# DAQ_Board.net
KiCad netlist of a schematic drawn in Altium Designer
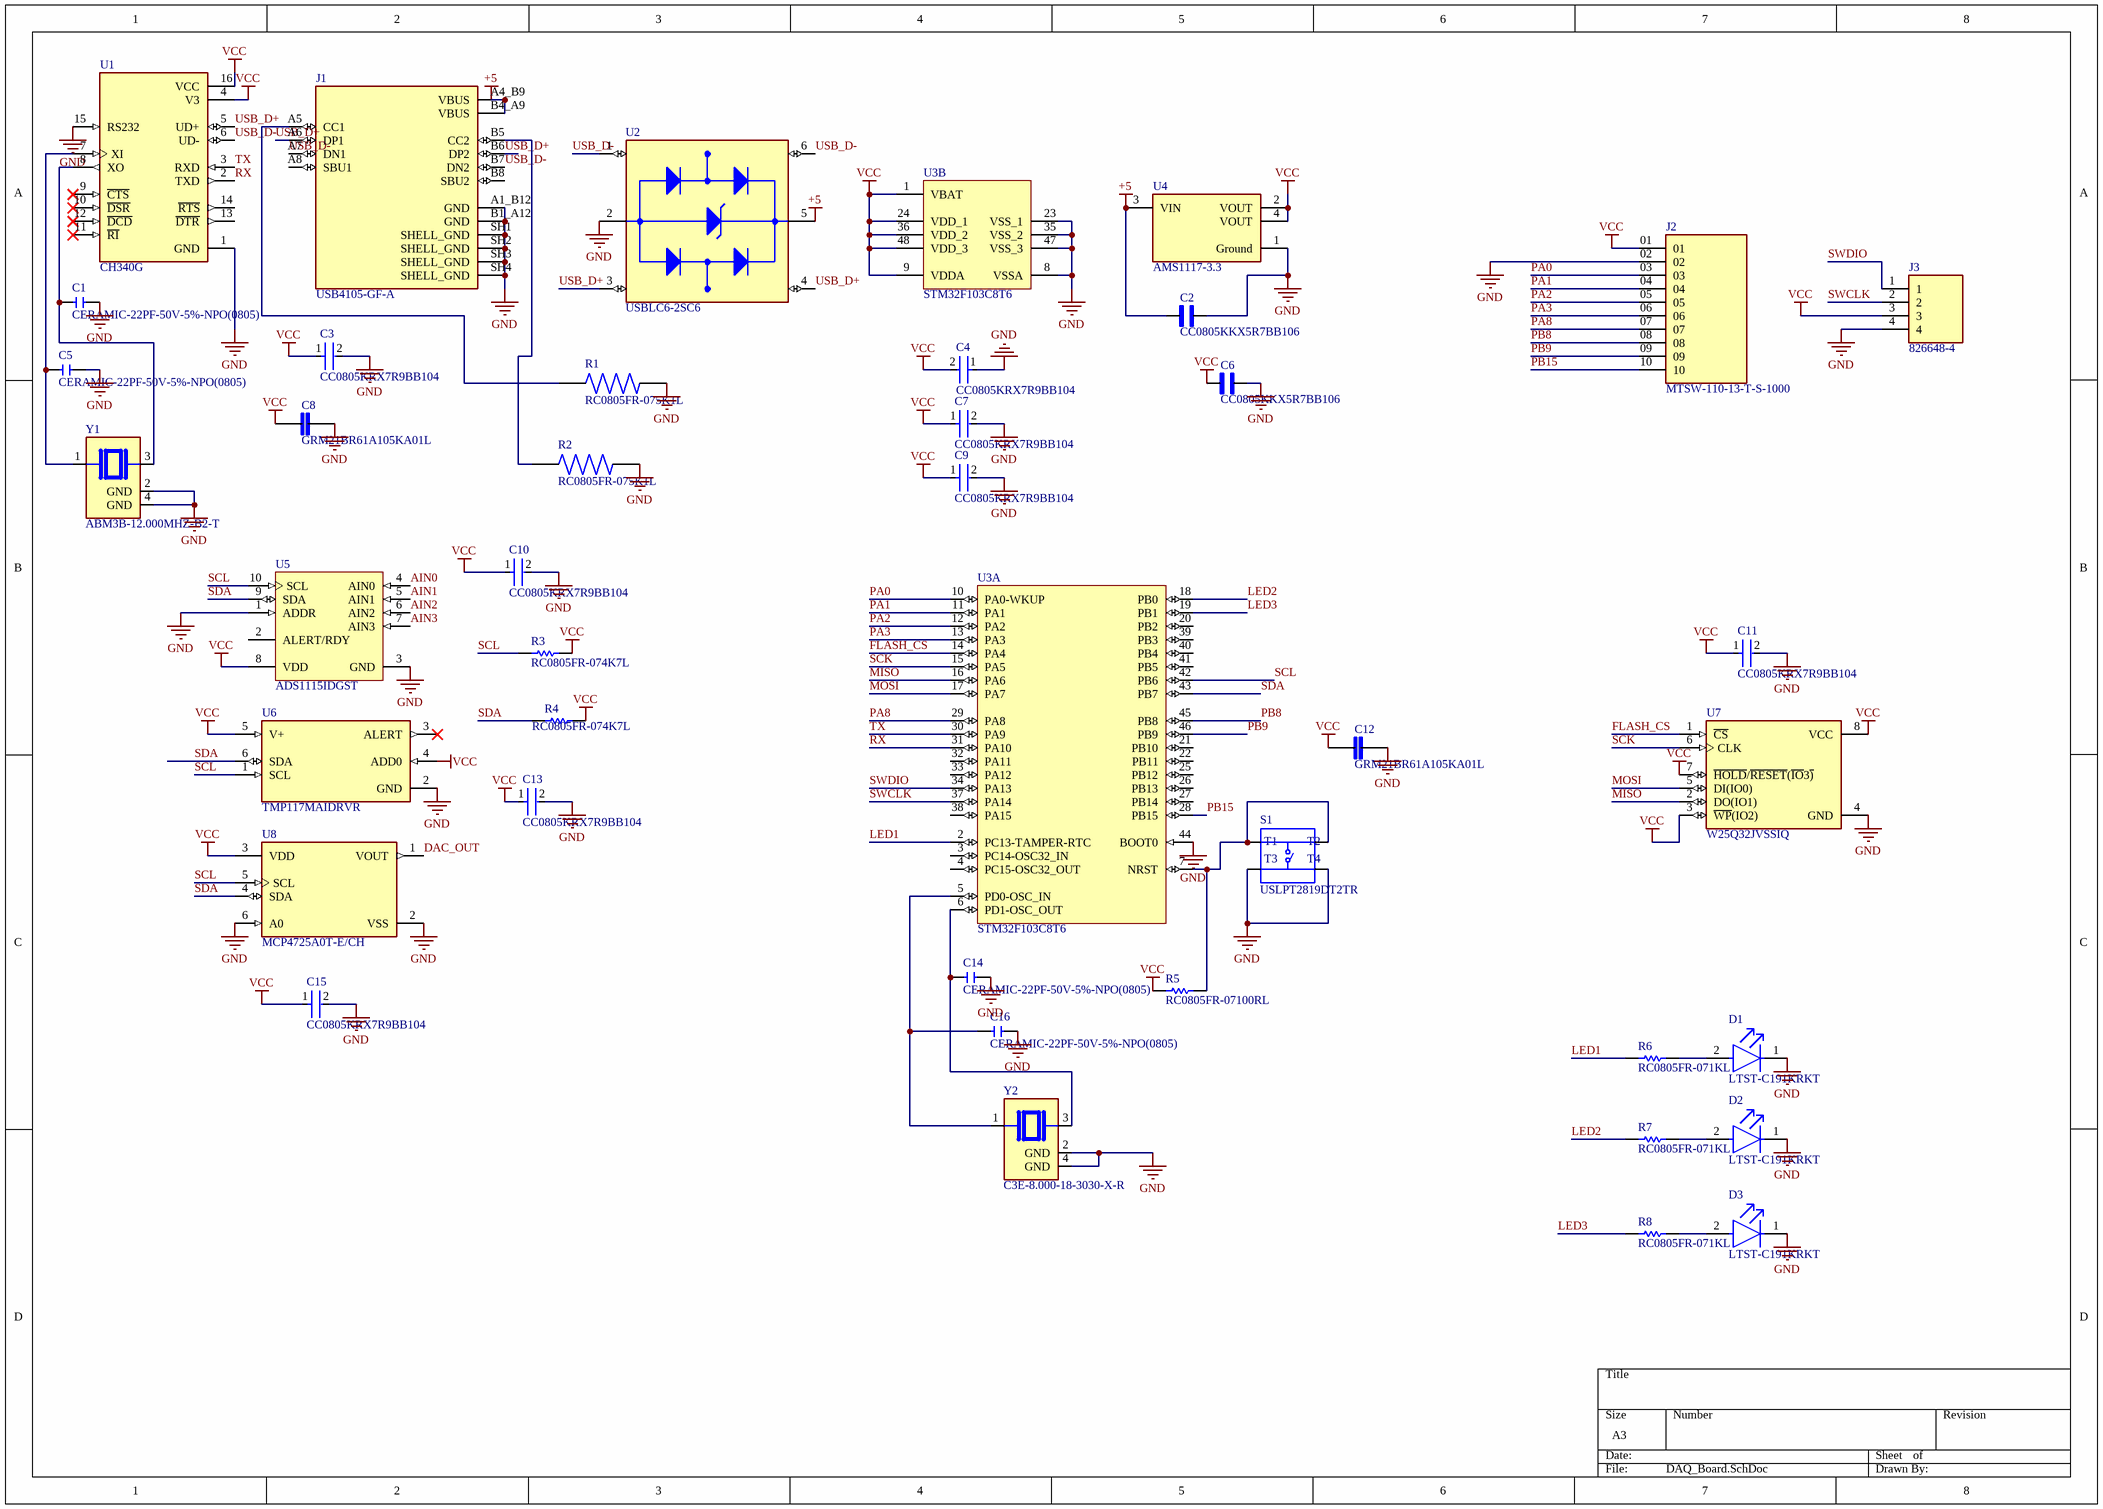
[diagram p0: DAQ_Board.SchDoc]

(export (version "E")
  (design (tool "Eeschema 10.0.6"))
  (components
    (comp (ref "C1")
      (value "CERAMIC-22PF-50V-5%-NPO(0805)")
      (footprint "C0805")
      (description "22 pF Â±5% 50V Ceramic Capacitor C0G, NP0 0805 (2012 Metric)")
      (fields (field (name "MF") "Yageo") (field (name "MP") "CC0805JRNPO9BN220"))
      (libsource (lib "CERAMIC-22PF-50V-5_-NPO_0805_") (part "CERAMIC-22PF-50V-5%-NPO(0805)"))
    )
    (comp (ref "C2")
      (value "CC0805KKX5R7BB106")
      (footprint "CAPC2012X70")
      (description "10 ÂµF Â±10% 16V Ceramic Capacitor X5R 0805 (2012 Metric)")
      (fields (field (name "MF") "Yageo"))
      (libsource (lib "CC0805KKX5R7BB106") (part "CC0805KKX5R7BB106"))
    )
    (comp (ref "C3")
      (value "CC0805KRX7R9BB104")
      (footprint "FP-CC0805-0_85-MFG")
      (description "CAP CER 0.1UF 50V X7R 0805")
      (fields (field (name "TOLERANCE") "0.1") (field (name "MANUFACTURER") "Yageo"))
      (libsource (lib "Altium Content Vault") (part "11868f565c42a9108669ba33697ecf6"))
    )
    (comp (ref "C4")
      (value "CC0805KRX7R9BB104")
      (footprint "FP-CC0805-0_85-MFG")
      (description "CAP CER 0.1UF 50V X7R 0805")
      (fields (field (name "TOLERANCE") "0.1") (field (name "MANUFACTURER") "Yageo"))
      (libsource (lib "Altium Content Vault") (part "11868f565c42a9108669ba33697ecf6"))
    )
    (comp (ref "C5")
      (value "CERAMIC-22PF-50V-5%-NPO(0805)")
      (footprint "C0805")
      (description "22 pF Â±5% 50V Ceramic Capacitor C0G, NP0 0805 (2012 Metric)")
      (fields (field (name "MF") "Yageo") (field (name "MP") "CC0805JRNPO9BN220"))
      (libsource (lib "CERAMIC-22PF-50V-5_-NPO_0805_") (part "CERAMIC-22PF-50V-5%-NPO(0805)"))
    )
    (comp (ref "C6")
      (value "CC0805KKX5R7BB106")
      (footprint "CAPC2012X70")
      (description "10 ÂµF Â±10% 16V Ceramic Capacitor X5R 0805 (2012 Metric)")
      (fields (field (name "MF") "Yageo"))
      (libsource (lib "CC0805KKX5R7BB106") (part "CC0805KKX5R7BB106"))
    )
    (comp (ref "C7")
      (value "CC0805KRX7R9BB104")
      (footprint "FP-CC0805-0_85-MFG")
      (description "CAP CER 0.1UF 50V X7R 0805")
      (fields (field (name "TOLERANCE") "0.1") (field (name "MANUFACTURER") "Yageo"))
      (libsource (lib "Altium Content Vault") (part "11868f565c42a9108669ba33697ecf6"))
    )
    (comp (ref "C8")
      (value "GRM21BR61A105KA01L")
      (footprint "CAPC2012X135N")
      (description "SMD Capacitor X5R(EIA) with Capacitance: 1.0uF Tol. 10%. Rated Voltage: 10Vdc")
      (fields (field (name "MF") "Murata"))
      (libsource (lib "GRM21BR61A105KA01L") (part "GRM21BR61A105KA01L"))
    )
    (comp (ref "C9")
      (value "CC0805KRX7R9BB104")
      (footprint "FP-CC0805-0_85-MFG")
      (description "CAP CER 0.1UF 50V X7R 0805")
      (fields (field (name "TOLERANCE") "0.1") (field (name "MANUFACTURER") "Yageo"))
      (libsource (lib "Altium Content Vault") (part "11868f565c42a9108669ba33697ecf6"))
    )
    (comp (ref "C10")
      (value "CC0805KRX7R9BB104")
      (footprint "FP-CC0805-0_85-MFG")
      (description "CAP CER 0.1UF 50V X7R 0805")
      (fields (field (name "TOLERANCE") "0.1") (field (name "MANUFACTURER") "Yageo"))
      (libsource (lib "Altium Content Vault") (part "11868f565c42a9108669ba33697ecf6"))
    )
    (comp (ref "C11")
      (value "CC0805KRX7R9BB104")
      (footprint "FP-CC0805-0_85-MFG")
      (description "CAP CER 0.1UF 50V X7R 0805")
      (fields (field (name "TOLERANCE") "0.1") (field (name "MANUFACTURER") "Yageo"))
      (libsource (lib "Altium Content Vault") (part "11868f565c42a9108669ba33697ecf6"))
    )
    (comp (ref "C12")
      (value "GRM21BR61A105KA01L")
      (footprint "CAPC2012X135N")
      (description "SMD Capacitor X5R(EIA) with Capacitance: 1.0uF Tol. 10%. Rated Voltage: 10Vdc")
      (fields (field (name "MF") "Murata"))
      (libsource (lib "GRM21BR61A105KA01L") (part "GRM21BR61A105KA01L"))
    )
    (comp (ref "C13")
      (value "CC0805KRX7R9BB104")
      (footprint "FP-CC0805-0_85-MFG")
      (description "CAP CER 0.1UF 50V X7R 0805")
      (fields (field (name "TOLERANCE") "0.1") (field (name "MANUFACTURER") "Yageo"))
      (libsource (lib "Altium Content Vault") (part "11868f565c42a9108669ba33697ecf6"))
    )
    (comp (ref "C14")
      (value "CERAMIC-22PF-50V-5%-NPO(0805)")
      (footprint "C0805")
      (description "22 pF Â±5% 50V Ceramic Capacitor C0G, NP0 0805 (2012 Metric)")
      (fields (field (name "MF") "Yageo") (field (name "MP") "CC0805JRNPO9BN220"))
      (libsource (lib "CERAMIC-22PF-50V-5_-NPO_0805_") (part "CERAMIC-22PF-50V-5%-NPO(0805)"))
    )
    (comp (ref "C15")
      (value "CC0805KRX7R9BB104")
      (footprint "FP-CC0805-0_85-MFG")
      (description "CAP CER 0.1UF 50V X7R 0805")
      (fields (field (name "TOLERANCE") "0.1") (field (name "MANUFACTURER") "Yageo"))
      (libsource (lib "Altium Content Vault") (part "11868f565c42a9108669ba33697ecf6"))
    )
    (comp (ref "C16")
      (value "CERAMIC-22PF-50V-5%-NPO(0805)")
      (footprint "C0805")
      (description "22 pF Â±5% 50V Ceramic Capacitor C0G, NP0 0805 (2012 Metric)")
      (fields (field (name "MF") "Yageo") (field (name "MP") "CC0805JRNPO9BN220"))
      (libsource (lib "CERAMIC-22PF-50V-5_-NPO_0805_") (part "CERAMIC-22PF-50V-5%-NPO(0805)"))
    )
    (comp (ref "D1")
      (value "LTST-C191KRKT")
      (footprint "FP-LTST-C191KRKT-MFG")
      (fields (field (name "VOLTAGE") "2V"))
      (libsource (lib "Altium Content Vault") (part "8706943c75ba83719d021d2fdc84c58"))
    )
    (comp (ref "D2")
      (value "LTST-C191KRKT")
      (footprint "FP-LTST-C191KRKT-MFG")
      (fields (field (name "VOLTAGE") "2V"))
      (libsource (lib "Altium Content Vault") (part "8706943c75ba83719d021d2fdc84c58"))
    )
    (comp (ref "D3")
      (value "LTST-C191KRKT")
      (footprint "FP-LTST-C191KRKT-MFG")
      (fields (field (name "VOLTAGE") "2V"))
      (libsource (lib "Altium Content Vault") (part "8706943c75ba83719d021d2fdc84c58"))
    )
    (comp (ref "J1")
      (value "USB4105-GF-A")
      (footprint "GCT_USB4105-GF-A")
      (fields (field (name "MF") "{'manufacturer': u'GCT'}"))
      (libsource (lib "USB4105-GF-A") (part "USB4105-GF-A"))
    )
    (comp (ref "J2")
      (value "MTSW-110-13-T-S-1000")
      (footprint "SAMTEC_MTSW-110-13-T-S-1000")
      (libsource (lib "MTSW-110-13-T-S-1000") (part "MTSW-110-13-T-S-1000"))
    )
    (comp (ref "J3")
      (value "826648-4")
      (footprint "TE_826648-4")
      (description "Connector Header Through Hole 4 position 0.100 (2.54mm)")
      (fields (field (name "MF") "TE Connectivity"))
      (libsource (lib "826648-4") (part "826648-4"))
    )
    (comp (ref "R1")
      (value "RC0805FR-075K1L")
      (footprint "RESC2012X60N")
      (fields (field (name "MF") "{'manufacturer': u'YAGEO'}"))
      (libsource (lib "RC0805FR-075K1L") (part "RC0805FR-075K1L"))
    )
    (comp (ref "R2")
      (value "RC0805FR-075K1L")
      (footprint "RESC2012X60N")
      (fields (field (name "MF") "{'manufacturer': u'YAGEO'}"))
      (libsource (lib "RC0805FR-075K1L") (part "RC0805FR-075K1L"))
    )
    (comp (ref "R3")
      (value "RC0805FR-074K7L")
      (footprint "YAGO-RC0805_M")
      (fields (field (name "TOLERANCE") "+/- 1%") (field (name "POWER") "0.125 W"))
      (libsource (lib "Altium Content Vault") (part "YAGO-RES-2"))
    )
    (comp (ref "R4")
      (value "RC0805FR-074K7L")
      (footprint "YAGO-RC0805_M")
      (fields (field (name "TOLERANCE") "+/- 1%") (field (name "POWER") "0.125 W"))
      (libsource (lib "Altium Content Vault") (part "YAGO-RES-2"))
    )
    (comp (ref "R5")
      (value "RC0805FR-07100RL")
      (footprint "RESC2013X60X35ML10T20")
      (description "Chip Resistor, 100 Ohm, +/-1%, 0.125 W, -55 to 155 degC, 0805 (2012 Metric), RoHS, Tape and Reel")
      (fields (field (name "TOLERANCE") "1%") (field (name "MANUFACTURER") "Yageo"))
      (libsource (lib "Altium Content Vault") (part "RES-2"))
    )
    (comp (ref "R6")
      (value "RC0805FR-071KL")
      (footprint "RESC2013X60X35ML10T20")
      (description "Chip Resistor, 1 KOhm, +/- 1%, 125 mW, -55 to 155 degC, 0805 (2012 Metric), RoHS, Tape and Reel")
      (fields (field (name "TOLERANCE") "1%") (field (name "MANUFACTURER") "Yageo"))
      (libsource (lib "Altium Content Vault") (part "RES-2"))
    )
    (comp (ref "R7")
      (value "RC0805FR-071KL")
      (footprint "RESC2013X60X35ML10T20")
      (description "Chip Resistor, 1 KOhm, +/- 1%, 125 mW, -55 to 155 degC, 0805 (2012 Metric), RoHS, Tape and Reel")
      (fields (field (name "TOLERANCE") "1%") (field (name "MANUFACTURER") "Yageo"))
      (libsource (lib "Altium Content Vault") (part "RES-2"))
    )
    (comp (ref "R8")
      (value "RC0805FR-071KL")
      (footprint "RESC2013X60X35ML10T20")
      (description "Chip Resistor, 1 KOhm, +/- 1%, 125 mW, -55 to 155 degC, 0805 (2012 Metric), RoHS, Tape and Reel")
      (fields (field (name "TOLERANCE") "1%") (field (name "MANUFACTURER") "Yageo"))
      (libsource (lib "Altium Content Vault") (part "RES-2"))
    )
    (comp (ref "S1")
      (value "USLPT2819DT2TR")
      (footprint "SW_USLPT2819DT2TR")
      (description "TACT ULTRA TB 2.8X1.9X0.6 160GF")
      (libsource (lib "USLPT2819DT2TR") (part "USLPT2819DT2TR"))
    )
    (comp (ref "U1")
      (value "CH340G")
      (footprint "SOIC127P600X180-16N")
      (description "USB Interface Integrated Circuit")
      (fields (field (name "MP") "Ch340G") (field (name "MF") "WCH"))
      (libsource (lib "CH340G") (part "CH340G"))
    )
    (comp (ref "U2")
      (value "USBLC6-2SC6")
      (footprint "SOT95P280X145-6N")
      (description "17V Clamp 5A (8/20Âµs) Ipp Tvs Diode Surface Mount SOT-23-6")
      (fields (field (name "MF") "STMicroelectronics"))
      (libsource (lib "USBLC6-2SC6") (part "USBLC6-2SC6"))
    )
    (comp (ref "U3")
      (value "STM32F103C8T6")
      (footprint "STM-LQFP48_L")
      (libsource (lib "Altium Content Vault") (part "MC-ARM-STM32F103X8_B-SQ48"))
    )
    (comp (ref "U4")
      (value "AMS1117-3.3")
      (footprint "FP-AMS1117-IPC_C")
      (description "LDO Voltage Regulators 1A, 3.3V")
      (fields
        (field (name "OCTOPART") "https://octopart.com/ams1117-3.3-advanced+monolithic+systems-25899300")
        (field (name "MANUFACTURER") "Advanced Monolithic Systems")
      )
      (libsource (lib "Altium Content Vault") (part "8bdbb5f8e77002000e30dd2845d0354"))
    )
    (comp (ref "U5")
      (value "ADS1115IDGST")
      (footprint "TI-DGS10_M")
      (fields (field (name "MANUFACTURER") "Texas Instruments"))
      (libsource (lib "Altium Content Vault") (part "TI-ADS1015_1115-10"))
    )
    (comp (ref "U6")
      (value "TMP117MAIDRVR")
      (footprint "FP-DRV0006B-IPC_C")
      (description "TEMPERATURE SENSOR")
      (libsource (lib "Altium Content Vault") (part "6af1b5b9c3f1ef8afed83eb3745dfc1"))
    )
    (comp (ref "U7")
      (value "W25Q32JVSSIQ")
      (footprint "SOIC127P790X216-8N")
      (description "FLASH - NOR Memory IC 32Mb (4M x 8) SPI - Quad I/O 133 MHz 8-SOIC")
      (fields (field (name "MF") "Winbond"))
      (libsource (lib "W25Q32JVSSIQ") (part "W25Q32JVSSIQ"))
    )
    (comp (ref "U8")
      (value "MCP4725A0T-E/CH")
      (footprint "FP-C04-028-CHY-IPC_A")
      (description "IC DAC 12BIT V-OUT SOT23-6")
      (libsource (lib "Altium Content Vault") (part "13d1b9b03173b6bd00baa384b893ce8"))
    )
    (comp (ref "Y1")
      (value "ABM3B-12.000MHZ-B2-T")
      (footprint "XTAL_ABM3B-12.000MHZ-B2-T")
      (description "12 MHz Â±20ppm Crystal 18pF 70 Ohms 4-SMD, No Lead")
      (fields (field (name "MF") "Abracon"))
      (libsource (lib "ABM3B-12.000MHZ-B2-T") (part "ABM3B-12.000MHZ-B2-T"))
    )
    (comp (ref "Y2")
      (value "C3E-8.000-18-3030-X-R")
      (footprint "XTAL_C3E-8.000-18-3030-X-R")
      (description "Crystal, 3.20mm x2.50mm,8MHz,18pF,-40-85C")
      (fields (field (name "MF") "Aker Technology USA"))
      (libsource (lib "C3E-8.000-18-3030-X-R") (part "C3E-8.000-18-3030-X-R"))
    )
  )
  (nets
    (net (code "1") (name "+5") (class "Default")
      (node (ref "C2") (pin "2") (pinfunction "2_2") (pintype "passive"))
      (node (ref "J1") (pin "A4_B9") (pinfunction "VBUS_A4_B9") (pintype "power_in"))
      (node (ref "J1") (pin "B4_A9") (pinfunction "VBUS_B4_A9") (pintype "power_in"))
      (node (ref "U2") (pin "5") (pinfunction "VBUS_5") (pintype "power_in"))
      (node (ref "U4") (pin "3") (pinfunction "VIN_3") (pintype "power_in"))
    )
    (net (code "2") (name "/AIN0") (class "Default")
      (node (ref "U5") (pin "4") (pinfunction "AIN0_4") (pintype "input"))
    )
    (net (code "3") (name "/AIN1") (class "Default")
      (node (ref "U5") (pin "5") (pinfunction "AIN1_5") (pintype "input"))
    )
    (net (code "4") (name "/AIN2") (class "Default")
      (node (ref "U5") (pin "6") (pinfunction "AIN2_6") (pintype "input"))
    )
    (net (code "5") (name "/AIN3") (class "Default")
      (node (ref "U5") (pin "7") (pinfunction "AIN3_7") (pintype "input"))
    )
    (net (code "6") (name "/DAC_OUT") (class "Default")
      (node (ref "U8") (pin "1") (pinfunction "VOUT_1") (pintype "output"))
    )
    (net (code "7") (name "/FLASH_CS") (class "Default")
      (node (ref "U3") (pin "14") (pinfunction "PA4_14") (pintype "bidirectional"))
      (node (ref "U7") (pin "1") (pinfunction "~{CS}_1") (pintype "input"))
    )
    (net (code "8") (name "/LED1") (class "Default")
      (node (ref "R6") (pin "1") (pinfunction "1_1") (pintype "passive"))
      (node (ref "U3") (pin "2") (pinfunction "PC13-TAMPER-RTC_2") (pintype "bidirectional"))
    )
    (net (code "9") (name "/LED2") (class "Default")
      (node (ref "R7") (pin "1") (pinfunction "1_1") (pintype "passive"))
      (node (ref "U3") (pin "18") (pinfunction "PB0_18") (pintype "bidirectional"))
    )
    (net (code "10") (name "/LED3") (class "Default")
      (node (ref "R8") (pin "1") (pinfunction "1_1") (pintype "passive"))
      (node (ref "U3") (pin "19") (pinfunction "PB1_19") (pintype "bidirectional"))
    )
    (net (code "11") (name "/MISO") (class "Default")
      (node (ref "U3") (pin "16") (pinfunction "PA6_16") (pintype "bidirectional"))
      (node (ref "U7") (pin "2") (pinfunction "DO(IO1)_2") (pintype "bidirectional"))
    )
    (net (code "12") (name "/MOSI") (class "Default")
      (node (ref "U3") (pin "17") (pinfunction "PA7_17") (pintype "bidirectional"))
      (node (ref "U7") (pin "5") (pinfunction "DI(IO0)_5") (pintype "bidirectional"))
    )
    (net (code "13") (name "/PA0") (class "Default")
      (node (ref "J2") (pin "03") (pinfunction "03_03") (pintype "passive"))
      (node (ref "U3") (pin "10") (pinfunction "PA0-WKUP_10") (pintype "bidirectional"))
    )
    (net (code "14") (name "/PA1") (class "Default")
      (node (ref "J2") (pin "04") (pinfunction "04_04") (pintype "passive"))
      (node (ref "U3") (pin "11") (pinfunction "PA1_11") (pintype "bidirectional"))
    )
    (net (code "15") (name "/PA2") (class "Default")
      (node (ref "J2") (pin "05") (pinfunction "05_05") (pintype "passive"))
      (node (ref "U3") (pin "12") (pinfunction "PA2_12") (pintype "bidirectional"))
    )
    (net (code "16") (name "/PA3") (class "Default")
      (node (ref "J2") (pin "06") (pinfunction "06_06") (pintype "passive"))
      (node (ref "U3") (pin "13") (pinfunction "PA3_13") (pintype "bidirectional"))
    )
    (net (code "17") (name "/PA8") (class "Default")
      (node (ref "J2") (pin "07") (pinfunction "07_07") (pintype "passive"))
      (node (ref "U3") (pin "29") (pinfunction "PA8_29") (pintype "bidirectional"))
    )
    (net (code "18") (name "/PB8") (class "Default")
      (node (ref "J2") (pin "08") (pinfunction "08_08") (pintype "passive"))
      (node (ref "U3") (pin "45") (pinfunction "PB8_45") (pintype "bidirectional"))
    )
    (net (code "19") (name "/PB9") (class "Default")
      (node (ref "J2") (pin "09") (pinfunction "09_09") (pintype "passive"))
      (node (ref "U3") (pin "46") (pinfunction "PB9_46") (pintype "bidirectional"))
    )
    (net (code "20") (name "/PB15") (class "Default")
      (node (ref "J2") (pin "10") (pinfunction "10_10") (pintype "passive"))
      (node (ref "U3") (pin "28") (pinfunction "PB15_28") (pintype "bidirectional"))
    )
    (net (code "21") (name "/RX") (class "Default")
      (node (ref "U1") (pin "2") (pinfunction "TXD_2") (pintype "output"))
      (node (ref "U3") (pin "31") (pinfunction "PA10_31") (pintype "bidirectional"))
    )
    (net (code "22") (name "/SCK") (class "Default")
      (node (ref "U3") (pin "15") (pinfunction "PA5_15") (pintype "bidirectional"))
      (node (ref "U7") (pin "6") (pinfunction "CLK_6") (pintype "input"))
    )
    (net (code "23") (name "/SCL") (class "Default")
      (node (ref "R3") (pin "1") (pinfunction "1_1") (pintype "passive"))
      (node (ref "U3") (pin "42") (pinfunction "PB6_42") (pintype "bidirectional"))
      (node (ref "U5") (pin "10") (pinfunction "SCL_10") (pintype "input"))
      (node (ref "U6") (pin "1") (pinfunction "SCL_1") (pintype "input"))
      (node (ref "U8") (pin "5") (pinfunction "SCL_5") (pintype "input"))
    )
    (net (code "24") (name "/SDA") (class "Default")
      (node (ref "R4") (pin "1") (pinfunction "1_1") (pintype "passive"))
      (node (ref "U3") (pin "43") (pinfunction "PB7_43") (pintype "bidirectional"))
      (node (ref "U5") (pin "9") (pinfunction "SDA_9") (pintype "bidirectional"))
      (node (ref "U6") (pin "6") (pinfunction "SDA_6") (pintype "bidirectional"))
      (node (ref "U8") (pin "4") (pinfunction "SDA_4") (pintype "bidirectional"))
    )
    (net (code "25") (name "/SWCLK") (class "Default")
      (node (ref "J3") (pin "2") (pinfunction "2_2") (pintype "passive"))
      (node (ref "U3") (pin "37") (pinfunction "PA14_37") (pintype "bidirectional"))
    )
    (net (code "26") (name "/SWDIO") (class "Default")
      (node (ref "J3") (pin "1") (pinfunction "1_1") (pintype "passive"))
      (node (ref "U3") (pin "34") (pinfunction "PA13_34") (pintype "bidirectional"))
    )
    (net (code "27") (name "/TX") (class "Default")
      (node (ref "U1") (pin "3") (pinfunction "RXD_3") (pintype "input"))
      (node (ref "U3") (pin "30") (pinfunction "PA9_30") (pintype "bidirectional"))
    )
    (net (code "28") (name "/USB_D+") (class "Default")
      (node (ref "J1") (pin "A6") (pinfunction "DP1_A6") (pintype "bidirectional"))
      (node (ref "J1") (pin "B6") (pinfunction "DP2_B6") (pintype "bidirectional"))
      (node (ref "U1") (pin "5") (pinfunction "UD+_5") (pintype "bidirectional"))
      (node (ref "U2") (pin "3") (pinfunction "I/O2_IN_3") (pintype "bidirectional"))
      (node (ref "U2") (pin "4") (pinfunction "I/O2_OUT_4") (pintype "bidirectional"))
    )
    (net (code "29") (name "/USB_D-") (class "Default")
      (node (ref "J1") (pin "A7") (pinfunction "DN1_A7") (pintype "bidirectional"))
      (node (ref "J1") (pin "B7") (pinfunction "DN2_B7") (pintype "bidirectional"))
      (node (ref "U1") (pin "6") (pinfunction "UD-_6") (pintype "bidirectional"))
      (node (ref "U2") (pin "1") (pinfunction "I/O1_IN_1") (pintype "bidirectional"))
      (node (ref "U2") (pin "6") (pinfunction "I/O1_OUT_6") (pintype "bidirectional"))
    )
    (net (code "30") (name "GND") (class "Default")
      (node (ref "C1") (pin "2") (pinfunction "2_2") (pintype "passive"))
      (node (ref "C10") (pin "2") (pinfunction "2_2") (pintype "passive"))
      (node (ref "C11") (pin "2") (pinfunction "2_2") (pintype "passive"))
      (node (ref "C12") (pin "2") (pinfunction "2_2") (pintype "passive"))
      (node (ref "C13") (pin "2") (pinfunction "2_2") (pintype "passive"))
      (node (ref "C14") (pin "2") (pinfunction "2_2") (pintype "passive"))
      (node (ref "C15") (pin "2") (pinfunction "2_2") (pintype "passive"))
      (node (ref "C16") (pin "2") (pinfunction "2_2") (pintype "passive"))
      (node (ref "C2") (pin "1") (pinfunction "1_1") (pintype "passive"))
      (node (ref "C3") (pin "2") (pinfunction "2_2") (pintype "passive"))
      (node (ref "C4") (pin "1") (pinfunction "1_1") (pintype "passive"))
      (node (ref "C5") (pin "2") (pinfunction "2_2") (pintype "passive"))
      (node (ref "C6") (pin "1") (pinfunction "1_1") (pintype "passive"))
      (node (ref "C7") (pin "2") (pinfunction "2_2") (pintype "passive"))
      (node (ref "C8") (pin "2") (pinfunction "2_2") (pintype "passive"))
      (node (ref "C9") (pin "2") (pinfunction "2_2") (pintype "passive"))
      (node (ref "D1") (pin "1") (pinfunction "C_1") (pintype "passive"))
      (node (ref "D2") (pin "1") (pinfunction "C_1") (pintype "passive"))
      (node (ref "D3") (pin "1") (pinfunction "C_1") (pintype "passive"))
      (node (ref "J1") (pin "A1_B12") (pinfunction "GND_A1_B12") (pintype "power_in"))
      (node (ref "J1") (pin "B1_A12") (pinfunction "GND_B1_A12") (pintype "power_in"))
      (node (ref "J1") (pin "SH1") (pinfunction "SHELL_GND_SH1") (pintype "power_in"))
      (node (ref "J1") (pin "SH2") (pinfunction "SHELL_GND_SH2") (pintype "power_in"))
      (node (ref "J1") (pin "SH3") (pinfunction "SHELL_GND_SH3") (pintype "power_in"))
      (node (ref "J1") (pin "SH4") (pinfunction "SHELL_GND_SH4") (pintype "power_in"))
      (node (ref "J2") (pin "02") (pinfunction "02_02") (pintype "passive"))
      (node (ref "J3") (pin "4") (pinfunction "4_4") (pintype "passive"))
      (node (ref "R1") (pin "2") (pinfunction "2_2") (pintype "passive"))
      (node (ref "R2") (pin "2") (pinfunction "2_2") (pintype "passive"))
      (node (ref "S1") (pin "3") (pinfunction "T3_3") (pintype "passive"))
      (node (ref "S1") (pin "4") (pinfunction "T4_4") (pintype "passive"))
      (node (ref "U1") (pin "1") (pinfunction "GND_1") (pintype "power_in"))
      (node (ref "U1") (pin "15") (pinfunction "RS232_15") (pintype "input"))
      (node (ref "U2") (pin "2") (pinfunction "GND_2") (pintype "power_in"))
      (node (ref "U3") (pin "23") (pinfunction "VSS_1_23") (pintype "power_in"))
      (node (ref "U3") (pin "35") (pinfunction "VSS_2_35") (pintype "power_in"))
      (node (ref "U3") (pin "44") (pinfunction "BOOT0_44") (pintype "input"))
      (node (ref "U3") (pin "47") (pinfunction "VSS_3_47") (pintype "power_in"))
      (node (ref "U3") (pin "8") (pinfunction "VSSA_8") (pintype "power_in"))
      (node (ref "U4") (pin "1") (pinfunction "Ground_1") (pintype "power_in"))
      (node (ref "U5") (pin "1") (pinfunction "ADDR_1") (pintype "input"))
      (node (ref "U5") (pin "3") (pinfunction "GND_3") (pintype "power_in"))
      (node (ref "U6") (pin "2") (pinfunction "GND_2") (pintype "power_in"))
      (node (ref "U7") (pin "4") (pinfunction "GND_4") (pintype "power_in"))
      (node (ref "U8") (pin "2") (pinfunction "VSS_2") (pintype "power_in"))
      (node (ref "U8") (pin "6") (pinfunction "A0_6") (pintype "input"))
      (node (ref "Y1") (pin "2") (pinfunction "GND_2") (pintype "power_in"))
      (node (ref "Y1") (pin "4") (pinfunction "GND_4") (pintype "power_in"))
      (node (ref "Y2") (pin "2") (pinfunction "GND_2") (pintype "power_in"))
      (node (ref "Y2") (pin "4") (pinfunction "GND_4") (pintype "power_in"))
    )
    (net (code "31") (name "Net-(D1-A)") (class "Default")
      (node (ref "D1") (pin "2") (pinfunction "A_2") (pintype "passive"))
      (node (ref "R6") (pin "2") (pinfunction "2_2") (pintype "passive"))
    )
    (net (code "32") (name "Net-(D2-A)") (class "Default")
      (node (ref "D2") (pin "2") (pinfunction "A_2") (pintype "passive"))
      (node (ref "R7") (pin "2") (pinfunction "2_2") (pintype "passive"))
    )
    (net (code "33") (name "Net-(D3-A)") (class "Default")
      (node (ref "D3") (pin "2") (pinfunction "A_2") (pintype "passive"))
      (node (ref "R8") (pin "2") (pinfunction "2_2") (pintype "passive"))
    )
    (net (code "34") (name "Net-(J1-CC1)") (class "Default")
      (node (ref "J1") (pin "A5") (pinfunction "CC1_A5") (pintype "bidirectional"))
      (node (ref "R1") (pin "1") (pinfunction "1_1") (pintype "passive"))
    )
    (net (code "35") (name "Net-(J1-CC2)") (class "Default")
      (node (ref "J1") (pin "B5") (pinfunction "CC2_B5") (pintype "bidirectional"))
      (node (ref "R2") (pin "1") (pinfunction "1_1") (pintype "passive"))
    )
    (net (code "36") (name "Net-(S1-T1)") (class "Default")
      (node (ref "R5") (pin "2") (pinfunction "2_2") (pintype "passive"))
      (node (ref "S1") (pin "1") (pinfunction "T1_1") (pintype "passive"))
      (node (ref "S1") (pin "2") (pinfunction "T2_2") (pintype "passive"))
      (node (ref "U3") (pin "7") (pinfunction "NRST_7") (pintype "bidirectional"))
    )
    (net (code "37") (name "Net-(U1-XI)") (class "Default")
      (node (ref "C5") (pin "1") (pinfunction "1_1") (pintype "passive"))
      (node (ref "U1") (pin "7") (pinfunction "XI_7") (pintype "input"))
      (node (ref "Y1") (pin "1") (pinfunction "1_1") (pintype "passive"))
    )
    (net (code "38") (name "Net-(U1-XO)") (class "Default")
      (node (ref "C1") (pin "1") (pinfunction "1_1") (pintype "passive"))
      (node (ref "U1") (pin "8") (pinfunction "XO_8") (pintype "output"))
      (node (ref "Y1") (pin "3") (pinfunction "2_3") (pintype "passive"))
    )
    (net (code "39") (name "Net-(U3A-PD0-OSC_IN)") (class "Default")
      (node (ref "C16") (pin "1") (pinfunction "1_1") (pintype "passive"))
      (node (ref "U3") (pin "5") (pinfunction "PD0-OSC_IN_5") (pintype "bidirectional"))
      (node (ref "Y2") (pin "1") (pinfunction "1_1") (pintype "passive"))
    )
    (net (code "40") (name "Net-(U3A-PD1-OSC_OUT)") (class "Default")
      (node (ref "C14") (pin "1") (pinfunction "1_1") (pintype "passive"))
      (node (ref "U3") (pin "6") (pinfunction "PD1-OSC_OUT_6") (pintype "bidirectional"))
      (node (ref "Y2") (pin "3") (pinfunction "3_3") (pintype "passive"))
    )
    (net (code "41") (name "VCC") (class "Default")
      (node (ref "C10") (pin "1") (pinfunction "1_1") (pintype "passive"))
      (node (ref "C11") (pin "1") (pinfunction "1_1") (pintype "passive"))
      (node (ref "C12") (pin "1") (pinfunction "1_1") (pintype "passive"))
      (node (ref "C13") (pin "1") (pinfunction "1_1") (pintype "passive"))
      (node (ref "C15") (pin "1") (pinfunction "1_1") (pintype "passive"))
      (node (ref "C3") (pin "1") (pinfunction "1_1") (pintype "passive"))
      (node (ref "C4") (pin "2") (pinfunction "2_2") (pintype "passive"))
      (node (ref "C6") (pin "2") (pinfunction "2_2") (pintype "passive"))
      (node (ref "C7") (pin "1") (pinfunction "1_1") (pintype "passive"))
      (node (ref "C8") (pin "1") (pinfunction "1_1") (pintype "passive"))
      (node (ref "C9") (pin "1") (pinfunction "1_1") (pintype "passive"))
      (node (ref "J2") (pin "01") (pinfunction "01_01") (pintype "passive"))
      (node (ref "J3") (pin "3") (pinfunction "3_3") (pintype "passive"))
      (node (ref "R3") (pin "2") (pinfunction "2_2") (pintype "passive"))
      (node (ref "R4") (pin "2") (pinfunction "2_2") (pintype "passive"))
      (node (ref "R5") (pin "1") (pinfunction "1_1") (pintype "passive"))
      (node (ref "U1") (pin "16") (pinfunction "VCC_16") (pintype "power_in"))
      (node (ref "U1") (pin "4") (pinfunction "V3_4") (pintype "power_in"))
      (node (ref "U3") (pin "1") (pinfunction "VBAT_1") (pintype "power_in"))
      (node (ref "U3") (pin "24") (pinfunction "VDD_1_24") (pintype "power_in"))
      (node (ref "U3") (pin "36") (pinfunction "VDD_2_36") (pintype "power_in"))
      (node (ref "U3") (pin "48") (pinfunction "VDD_3_48") (pintype "power_in"))
      (node (ref "U3") (pin "9") (pinfunction "VDDA_9") (pintype "power_in"))
      (node (ref "U4") (pin "2") (pinfunction "VOUT_2") (pintype "passive"))
      (node (ref "U4") (pin "4") (pinfunction "VOUT_4") (pintype "passive"))
      (node (ref "U5") (pin "8") (pinfunction "VDD_8") (pintype "power_in"))
      (node (ref "U6") (pin "4") (pinfunction "ADD0_4") (pintype "input"))
      (node (ref "U6") (pin "5") (pinfunction "V+_5") (pintype "input"))
      (node (ref "U7") (pin "3") (pinfunction "~{WP}(IO2)_3") (pintype "bidirectional"))
      (node (ref "U7") (pin "7") (pinfunction "~{HOLD}/~{RESET}(~{IO}3~{)}_7") (pintype "bidirectional"))
      (node (ref "U7") (pin "8") (pinfunction "VCC_8") (pintype "power_in"))
      (node (ref "U8") (pin "3") (pinfunction "VDD_3") (pintype "power_in"))
    )
    (net (code "42") (name "unconnected-(J1-SBU1-PadA8)") (class "Default")
      (node (ref "J1") (pin "A8") (pinfunction "SBU1_A8") (pintype "bidirectional"))
    )
    (net (code "43") (name "unconnected-(J1-SBU2-PadB8)") (class "Default")
      (node (ref "J1") (pin "B8") (pinfunction "SBU2_B8") (pintype "bidirectional"))
    )
    (net (code "44") (name "unconnected-(U1-~{CTS}-Pad9)") (class "Default")
      (node (ref "U1") (pin "9") (pinfunction "~{CTS}_9") (pintype "input+no_connect"))
    )
    (net (code "45") (name "unconnected-(U1-~{DCD}-Pad12)") (class "Default")
      (node (ref "U1") (pin "12") (pinfunction "~{DCD}_12") (pintype "input+no_connect"))
    )
    (net (code "46") (name "unconnected-(U1-~{DSR}-Pad10)") (class "Default")
      (node (ref "U1") (pin "10") (pinfunction "~{DSR}_10") (pintype "input+no_connect"))
    )
    (net (code "47") (name "unconnected-(U1-~{DTR}-Pad13)") (class "Default")
      (node (ref "U1") (pin "13") (pinfunction "~{DTR}_13") (pintype "output"))
    )
    (net (code "48") (name "unconnected-(U1-~{RI}-Pad11)") (class "Default")
      (node (ref "U1") (pin "11") (pinfunction "~{RI}_11") (pintype "input+no_connect"))
    )
    (net (code "49") (name "unconnected-(U1-~{RTS}-Pad14)") (class "Default")
      (node (ref "U1") (pin "14") (pinfunction "~{RTS}_14") (pintype "output"))
    )
    (net (code "50") (name "unconnected-(U3A-PA11-Pad32)") (class "Default")
      (node (ref "U3") (pin "32") (pinfunction "PA11_32") (pintype "bidirectional"))
    )
    (net (code "51") (name "unconnected-(U3A-PA12-Pad33)") (class "Default")
      (node (ref "U3") (pin "33") (pinfunction "PA12_33") (pintype "bidirectional"))
    )
    (net (code "52") (name "unconnected-(U3A-PA15-Pad38)") (class "Default")
      (node (ref "U3") (pin "38") (pinfunction "PA15_38") (pintype "bidirectional"))
    )
    (net (code "53") (name "unconnected-(U3A-PB2-Pad20)") (class "Default")
      (node (ref "U3") (pin "20") (pinfunction "PB2_20") (pintype "bidirectional"))
    )
    (net (code "54") (name "unconnected-(U3A-PB3-Pad39)") (class "Default")
      (node (ref "U3") (pin "39") (pinfunction "PB3_39") (pintype "bidirectional"))
    )
    (net (code "55") (name "unconnected-(U3A-PB4-Pad40)") (class "Default")
      (node (ref "U3") (pin "40") (pinfunction "PB4_40") (pintype "bidirectional"))
    )
    (net (code "56") (name "unconnected-(U3A-PB5-Pad41)") (class "Default")
      (node (ref "U3") (pin "41") (pinfunction "PB5_41") (pintype "bidirectional"))
    )
    (net (code "57") (name "unconnected-(U3A-PB10-Pad21)") (class "Default")
      (node (ref "U3") (pin "21") (pinfunction "PB10_21") (pintype "bidirectional"))
    )
    (net (code "58") (name "unconnected-(U3A-PB11-Pad22)") (class "Default")
      (node (ref "U3") (pin "22") (pinfunction "PB11_22") (pintype "bidirectional"))
    )
    (net (code "59") (name "unconnected-(U3A-PB12-Pad25)") (class "Default")
      (node (ref "U3") (pin "25") (pinfunction "PB12_25") (pintype "bidirectional"))
    )
    (net (code "60") (name "unconnected-(U3A-PB13-Pad26)") (class "Default")
      (node (ref "U3") (pin "26") (pinfunction "PB13_26") (pintype "bidirectional"))
    )
    (net (code "61") (name "unconnected-(U3A-PB14-Pad27)") (class "Default")
      (node (ref "U3") (pin "27") (pinfunction "PB14_27") (pintype "bidirectional"))
    )
    (net (code "62") (name "unconnected-(U3A-PC14-OSC32_IN-Pad3)") (class "Default")
      (node (ref "U3") (pin "3") (pinfunction "PC14-OSC32_IN_3") (pintype "bidirectional"))
    )
    (net (code "63") (name "unconnected-(U3A-PC15-OSC32_OUT-Pad4)") (class "Default")
      (node (ref "U3") (pin "4") (pinfunction "PC15-OSC32_OUT_4") (pintype "bidirectional"))
    )
    (net (code "64") (name "unconnected-(U5-ALERT{slash}RDY-Pad2)") (class "Default")
      (node (ref "U5") (pin "2") (pinfunction "ALERT/RDY_2") (pintype "open_collector"))
    )
    (net (code "65") (name "unconnected-(U6-ALERT-Pad3)") (class "Default")
      (node (ref "U6") (pin "3") (pinfunction "ALERT_3") (pintype "output+no_connect"))
    )
  )
)
